# Toggle_Switch_Hub.net
KiCad netlist of a schematic drawn in EAGLE
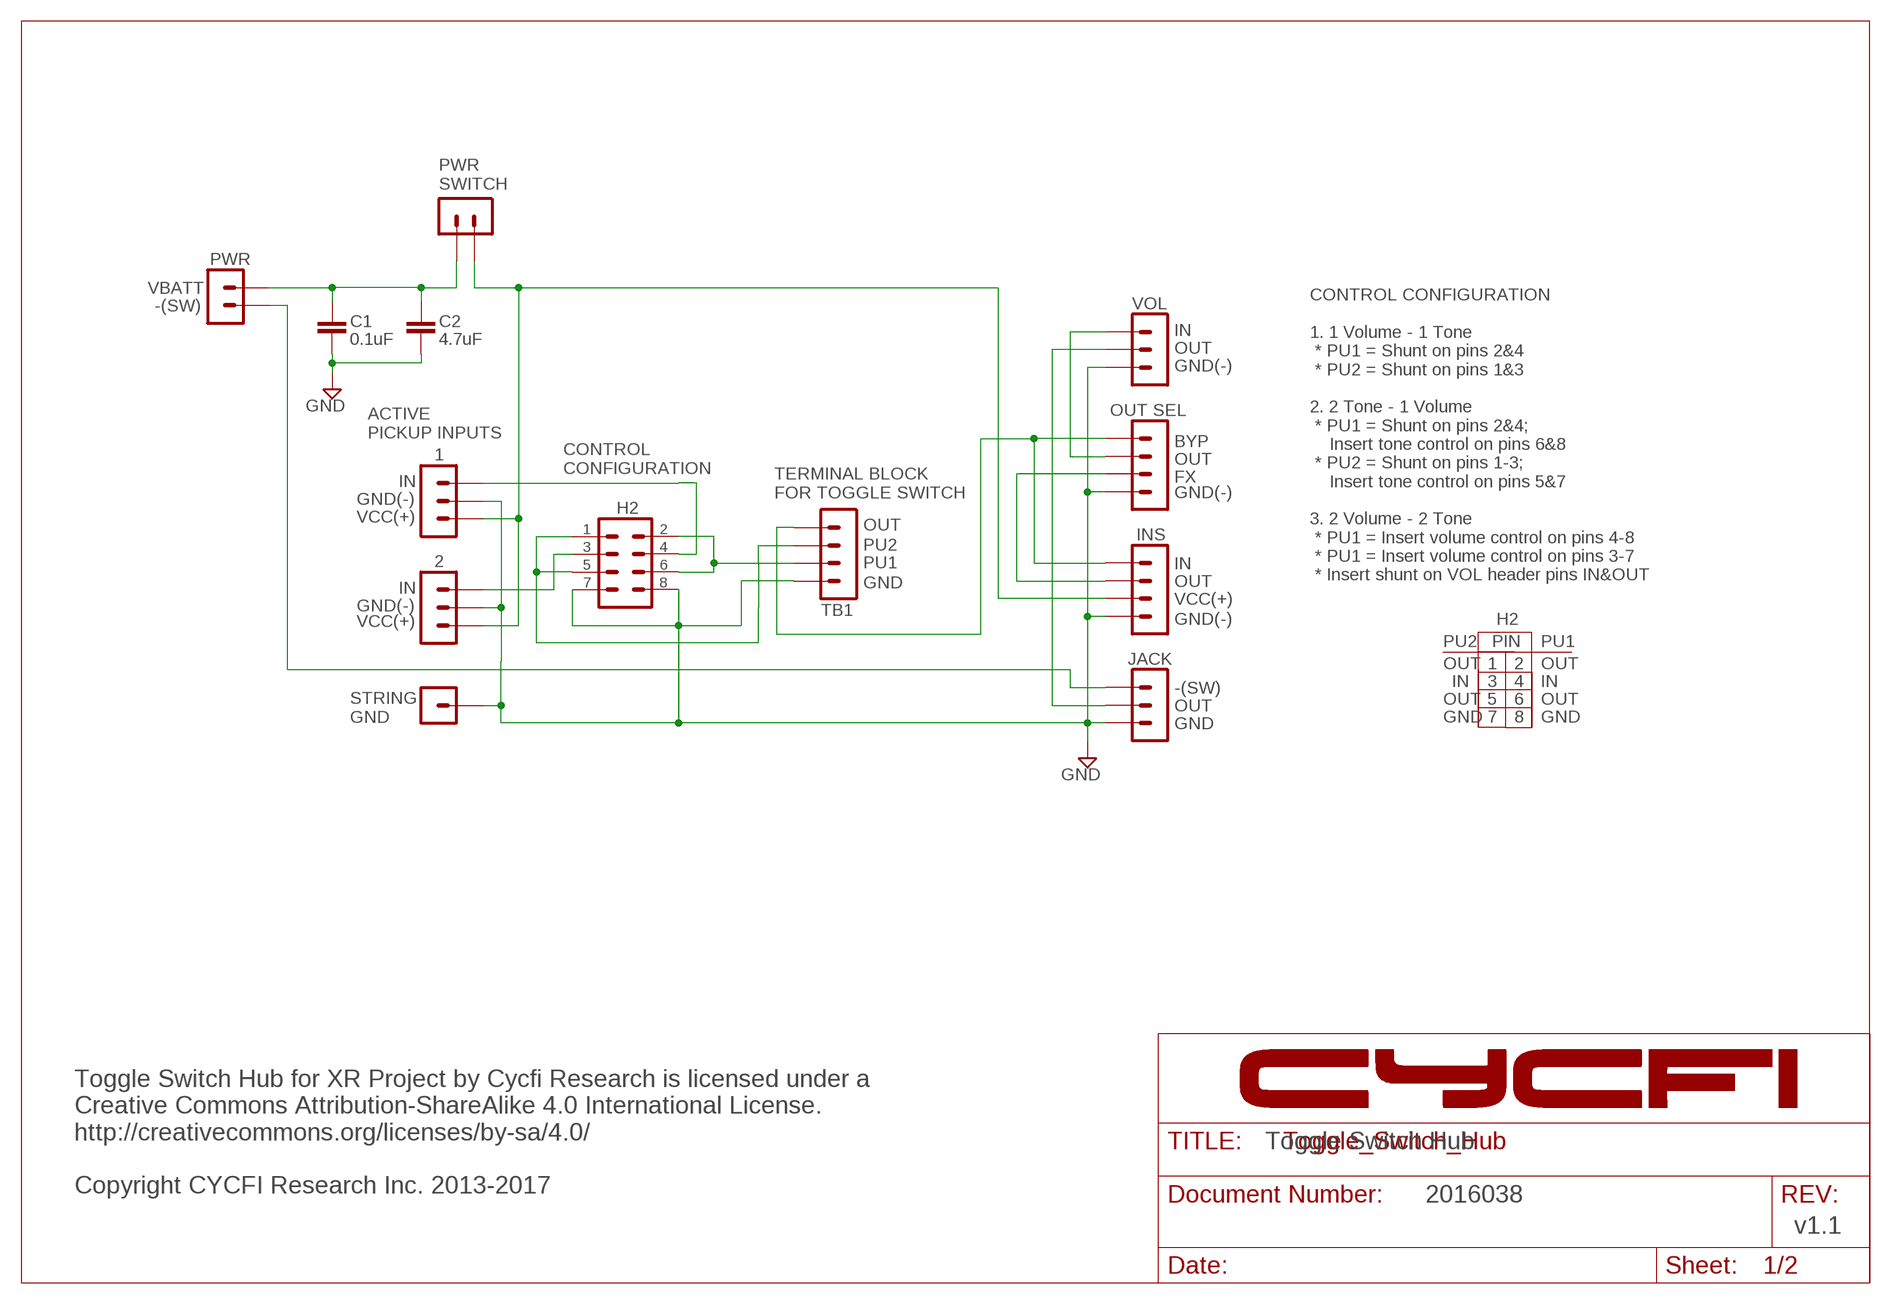
[diagram p0: schematic, sheet 1]
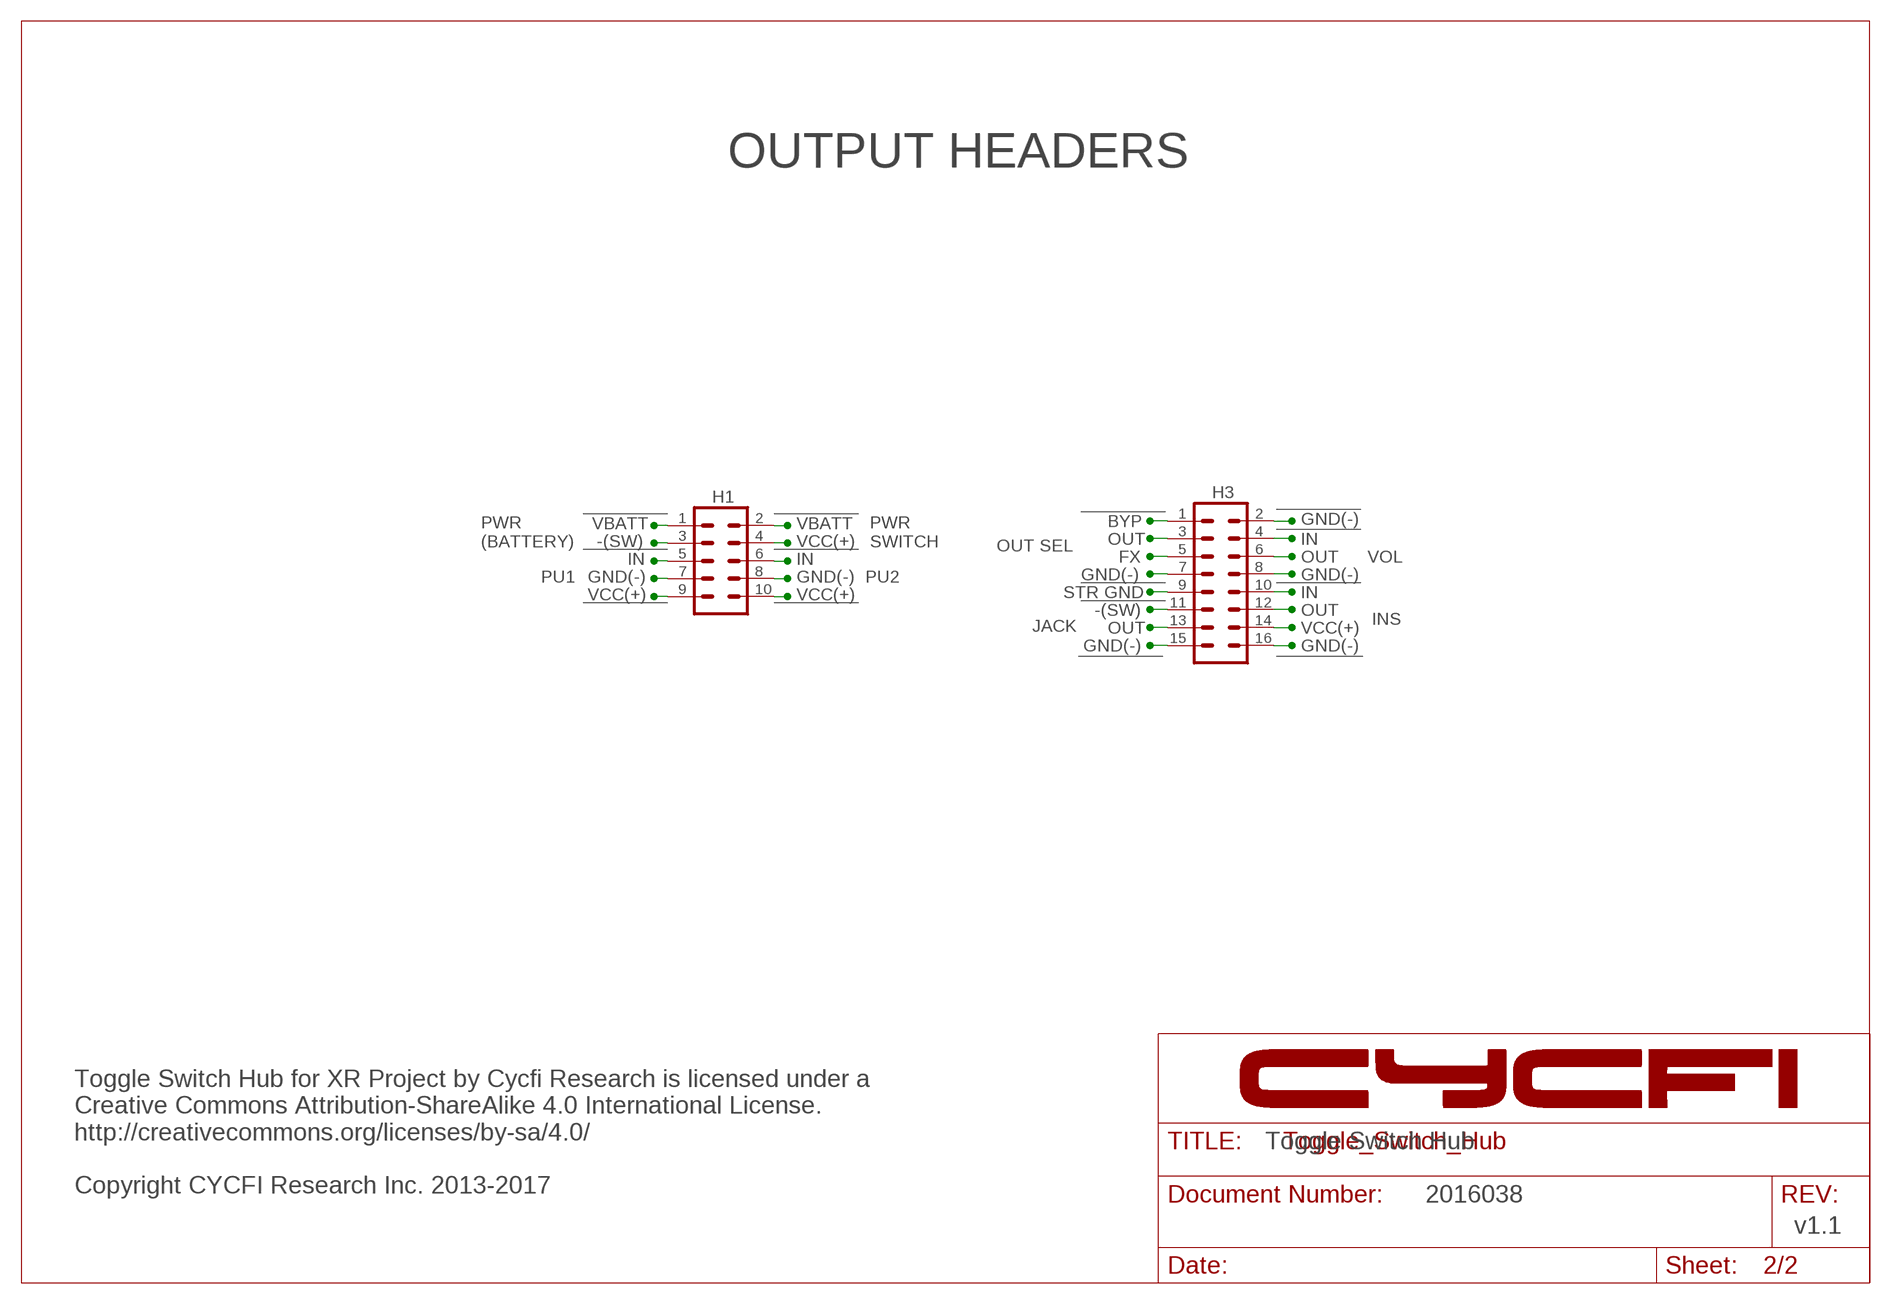
[diagram p1: schematic, sheet 2]

(export (version "E")
  (design (tool "Eeschema 10.0.6"))
  (components
    (comp (ref "H1")
      (value "MA05-2")
      (footprint "eagle-import:MA05-2")
      (libsource (lib "eagle-import") (part "MA05-2"))
    )
    (comp (ref "H3")
      (value "MA08-2")
      (footprint "eagle-import:MA08-2")
      (libsource (lib "eagle-import") (part "MA08-2"))
    )
    (comp (ref "C1")
      (value "0.1uF")
      (footprint "eagle-import:C0603")
      (libsource (lib "eagle-import") (part "C-EUC0603"))
    )
    (comp (ref "C2")
      (value "4.7uF")
      (footprint "eagle-import:C0603")
      (libsource (lib "eagle-import") (part "C-EUC0603"))
    )
    (comp (ref "H2")
      (value "MA04-2")
      (footprint "eagle-import:MA04-2")
      (libsource (lib "eagle-import") (part "MA04-2"))
    )
    (comp (ref "TB1")
      (value "282837-4_TERMINAL_BLOCK")
      (footprint "eagle-import:TERMINAL_BLOCK_4P_5.08MM")
      (libsource (lib "eagle-import") (part "282837-4_TERMINAL_BLOCK"))
    )
  )
  (nets
    (net (code "1") (name "BYP") (class "Default")
      (node (ref "H3") (pin "1") (pinfunction "1_1") (pintype "passive"))
      (node (ref "H3") (pin "10") (pinfunction "10_10") (pintype "passive"))
      (node (ref "TB1") (pin "P$4") (pinfunction "4_P$4") (pintype "passive"))
    )
    (net (code "2") (name "FX") (class "Default")
      (node (ref "H3") (pin "12") (pinfunction "12_12") (pintype "passive"))
      (node (ref "H3") (pin "5") (pinfunction "5_5") (pintype "passive"))
    )
    (net (code "3") (name "GND") (class "Default")
      (node (ref "C1") (pin "2") (pinfunction "2_2") (pintype "passive"))
      (node (ref "C2") (pin "2") (pinfunction "2_2") (pintype "passive"))
      (node (ref "H1") (pin "7") (pinfunction "7_7") (pintype "passive"))
      (node (ref "H1") (pin "8") (pinfunction "8_8") (pintype "passive"))
      (node (ref "H2") (pin "7") (pinfunction "7_7") (pintype "passive"))
      (node (ref "H2") (pin "8") (pinfunction "8_8") (pintype "passive"))
      (node (ref "H3") (pin "15") (pinfunction "15_15") (pintype "passive"))
      (node (ref "H3") (pin "16") (pinfunction "16_16") (pintype "passive"))
      (node (ref "H3") (pin "2") (pinfunction "2_2") (pintype "passive"))
      (node (ref "H3") (pin "7") (pinfunction "7_7") (pintype "passive"))
      (node (ref "H3") (pin "8") (pinfunction "8_8") (pintype "passive"))
      (node (ref "H3") (pin "9") (pinfunction "9_9") (pintype "passive"))
      (node (ref "TB1") (pin "P$1") (pinfunction "1_P$1") (pintype "passive"))
    )
    (net (code "4") (name "Net-(TB1-2)") (class "Default")
      (node (ref "H2") (pin "2") (pinfunction "2_2") (pintype "passive"))
      (node (ref "H2") (pin "6") (pinfunction "6_6") (pintype "passive"))
      (node (ref "TB1") (pin "P$2") (pinfunction "2_P$2") (pintype "passive"))
    )
    (net (code "5") (name "Net-(TB1-3)") (class "Default")
      (node (ref "H2") (pin "1") (pinfunction "1_1") (pintype "passive"))
      (node (ref "H2") (pin "5") (pinfunction "5_5") (pintype "passive"))
      (node (ref "TB1") (pin "P$3") (pinfunction "3_P$3") (pintype "passive"))
    )
    (net (code "6") (name "OUT") (class "Default")
      (node (ref "H3") (pin "3") (pinfunction "3_3") (pintype "passive"))
      (node (ref "H3") (pin "4") (pinfunction "4_4") (pintype "passive"))
    )
    (net (code "7") (name "OUT(VOL)") (class "Default")
      (node (ref "H3") (pin "13") (pinfunction "13_13") (pintype "passive"))
      (node (ref "H3") (pin "6") (pinfunction "6_6") (pintype "passive"))
    )
    (net (code "8") (name "PU1") (class "Default")
      (node (ref "H1") (pin "5") (pinfunction "5_5") (pintype "passive"))
      (node (ref "H2") (pin "4") (pinfunction "4_4") (pintype "passive"))
    )
    (net (code "9") (name "PU2") (class "Default")
      (node (ref "H1") (pin "6") (pinfunction "6_6") (pintype "passive"))
      (node (ref "H2") (pin "3") (pinfunction "3_3") (pintype "passive"))
    )
    (net (code "10") (name "SW") (class "Default")
      (node (ref "H1") (pin "3") (pinfunction "3_3") (pintype "passive"))
      (node (ref "H3") (pin "11") (pinfunction "11_11") (pintype "passive"))
    )
    (net (code "11") (name "VCC") (class "Default")
      (node (ref "C1") (pin "1") (pinfunction "1_1") (pintype "passive"))
      (node (ref "C2") (pin "1") (pinfunction "1_1") (pintype "passive"))
      (node (ref "H1") (pin "1") (pinfunction "1_1") (pintype "passive"))
      (node (ref "H1") (pin "2") (pinfunction "2_2") (pintype "passive"))
    )
    (net (code "12") (name "VIN") (class "Default")
      (node (ref "H1") (pin "10") (pinfunction "10_10") (pintype "passive"))
      (node (ref "H1") (pin "4") (pinfunction "4_4") (pintype "passive"))
      (node (ref "H1") (pin "9") (pinfunction "9_9") (pintype "passive"))
      (node (ref "H3") (pin "14") (pinfunction "14_14") (pintype "passive"))
    )
  )
)
